# Constant_Register.net
KiCad netlist of a schematic drawn in EAGLE
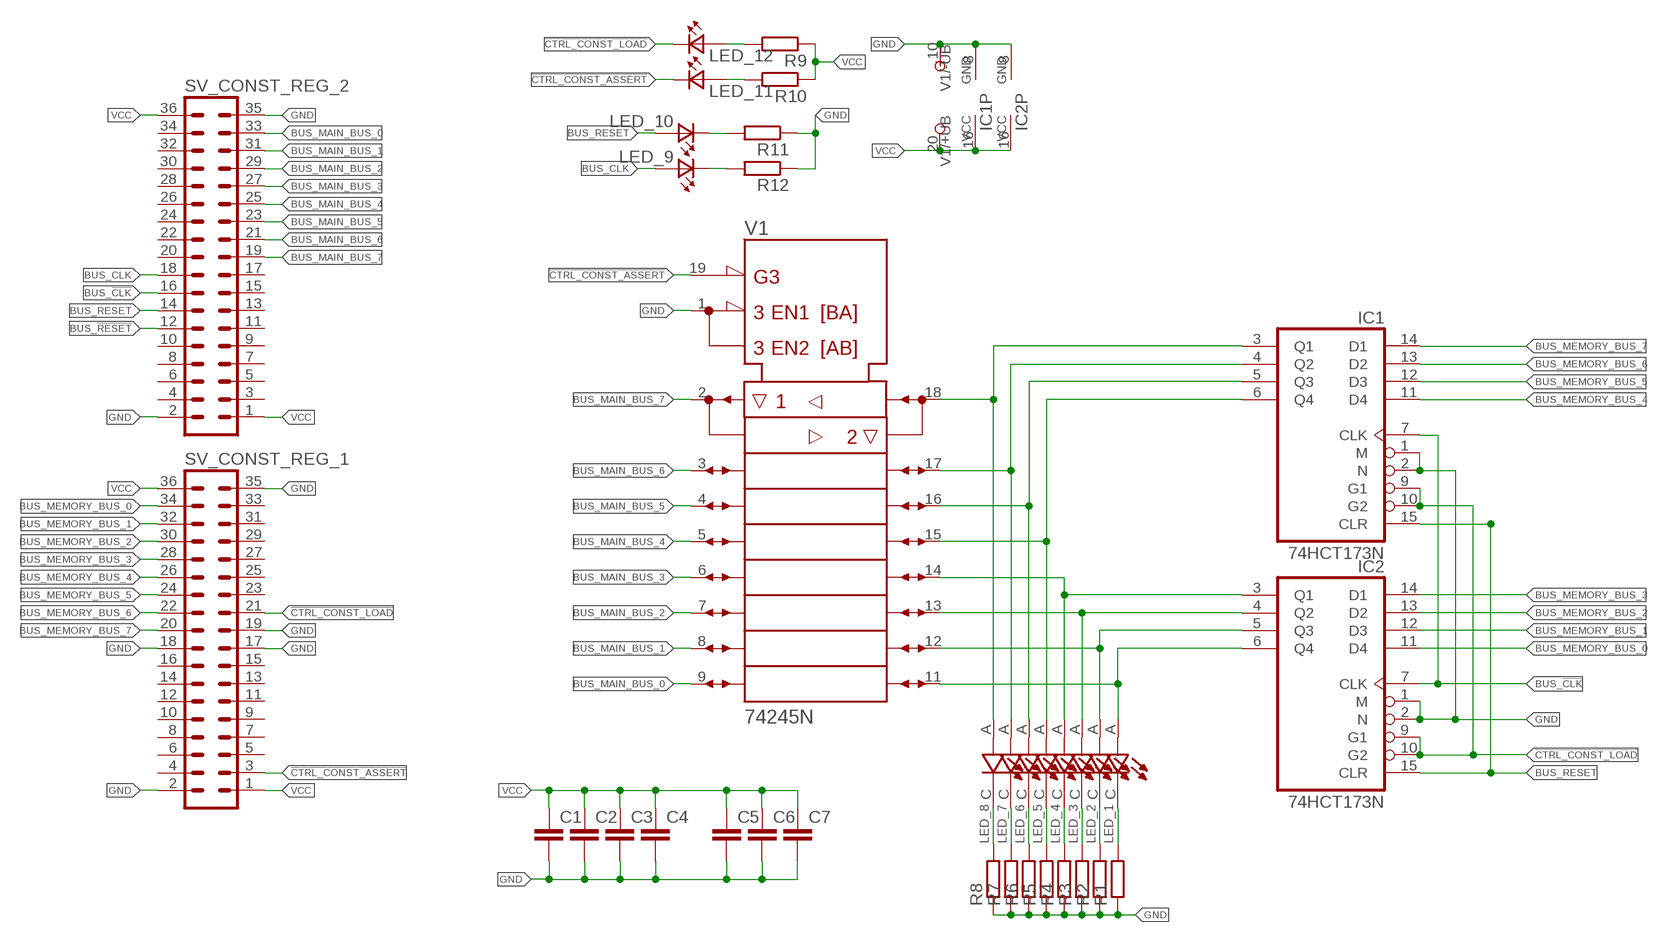
[diagram p0: schematic, sheet 1]

(export (version "E")
  (design (tool "Eeschema 10.0.6"))
  (components
    (comp (ref "C1")
      (value "C-EUC0805")
      (footprint "eagle-import:C0805")
      (libsource (lib "eagle-import") (part "C-EUC0805"))
    )
    (comp (ref "C2")
      (value "C-EUC0805")
      (footprint "eagle-import:C0805")
      (libsource (lib "eagle-import") (part "C-EUC0805"))
    )
    (comp (ref "C3")
      (value "C-EUC0805")
      (footprint "eagle-import:C0805")
      (libsource (lib "eagle-import") (part "C-EUC0805"))
    )
    (comp (ref "C4")
      (value "C-EUC0805")
      (footprint "eagle-import:C0805")
      (libsource (lib "eagle-import") (part "C-EUC0805"))
    )
    (comp (ref "C5")
      (value "C-EUC0805")
      (footprint "eagle-import:C0805")
      (libsource (lib "eagle-import") (part "C-EUC0805"))
    )
    (comp (ref "C6")
      (value "C-EUC0805")
      (footprint "eagle-import:C0805")
      (libsource (lib "eagle-import") (part "C-EUC0805"))
    )
    (comp (ref "C7")
      (value "C-EUC0805")
      (footprint "eagle-import:C0805")
      (libsource (lib "eagle-import") (part "C-EUC0805"))
    )
    (comp (ref "IC1")
      (value "74HCT173N")
      (footprint "eagle-import:DIL16")
      (libsource (lib "eagle-import") (part "74173NHCT"))
    )
    (comp (ref "IC2")
      (value "74HCT173N")
      (footprint "eagle-import:DIL16")
      (libsource (lib "eagle-import") (part "74173NHCT"))
    )
    (comp (ref "LED_1")
      (value "LTST-C193KRKT-5A")
      (footprint "eagle-import:LEDC1608X45N")
      (fields (field (name "MANUFACTURER") "Lite-On"))
      (libsource (lib "eagle-import") (part "LTST-C193KRKT-5A"))
    )
    (comp (ref "LED_2")
      (value "LTST-C193KRKT-5A")
      (footprint "eagle-import:LEDC1608X45N")
      (fields (field (name "MANUFACTURER") "Lite-On"))
      (libsource (lib "eagle-import") (part "LTST-C193KRKT-5A"))
    )
    (comp (ref "LED_3")
      (value "LTST-C193KRKT-5A")
      (footprint "eagle-import:LEDC1608X45N")
      (fields (field (name "MANUFACTURER") "Lite-On"))
      (libsource (lib "eagle-import") (part "LTST-C193KRKT-5A"))
    )
    (comp (ref "LED_4")
      (value "LTST-C193KRKT-5A")
      (footprint "eagle-import:LEDC1608X45N")
      (fields (field (name "MANUFACTURER") "Lite-On"))
      (libsource (lib "eagle-import") (part "LTST-C193KRKT-5A"))
    )
    (comp (ref "LED_5")
      (value "LTST-C193KRKT-5A")
      (footprint "eagle-import:LEDC1608X45N")
      (fields (field (name "MANUFACTURER") "Lite-On"))
      (libsource (lib "eagle-import") (part "LTST-C193KRKT-5A"))
    )
    (comp (ref "LED_6")
      (value "LTST-C193KRKT-5A")
      (footprint "eagle-import:LEDC1608X45N")
      (fields (field (name "MANUFACTURER") "Lite-On"))
      (libsource (lib "eagle-import") (part "LTST-C193KRKT-5A"))
    )
    (comp (ref "LED_7")
      (value "LTST-C193KRKT-5A")
      (footprint "eagle-import:LEDC1608X45N")
      (fields (field (name "MANUFACTURER") "Lite-On"))
      (libsource (lib "eagle-import") (part "LTST-C193KRKT-5A"))
    )
    (comp (ref "LED_8")
      (value "LTST-C193KRKT-5A")
      (footprint "eagle-import:LEDC1608X45N")
      (fields (field (name "MANUFACTURER") "Lite-On"))
      (libsource (lib "eagle-import") (part "LTST-C193KRKT-5A"))
    )
    (comp (ref "LED_9")
      (value "LTST-C193TBKT-5A")
      (footprint "eagle-import:0603")
      (libsource (lib "eagle-import") (part "LTST-C193TBKT-5A"))
    )
    (comp (ref "LED_10")
      (value "LTST-C193TBKT-5A")
      (footprint "eagle-import:0603")
      (libsource (lib "eagle-import") (part "LTST-C193TBKT-5A"))
    )
    (comp (ref "LED_11")
      (value "LTST-C193TBKT-5A")
      (footprint "eagle-import:0603")
      (libsource (lib "eagle-import") (part "LTST-C193TBKT-5A"))
    )
    (comp (ref "LED_12")
      (value "LTST-C193TBKT-5A")
      (footprint "eagle-import:0603")
      (libsource (lib "eagle-import") (part "LTST-C193TBKT-5A"))
    )
    (comp (ref "R1")
      (value "R-EU_R0805")
      (footprint "eagle-import:R0805")
      (libsource (lib "eagle-import") (part "R-EU_R0805"))
    )
    (comp (ref "R2")
      (value "R-EU_R0805")
      (footprint "eagle-import:R0805")
      (libsource (lib "eagle-import") (part "R-EU_R0805"))
    )
    (comp (ref "R3")
      (value "R-EU_R0805")
      (footprint "eagle-import:R0805")
      (libsource (lib "eagle-import") (part "R-EU_R0805"))
    )
    (comp (ref "R4")
      (value "R-EU_R0805")
      (footprint "eagle-import:R0805")
      (libsource (lib "eagle-import") (part "R-EU_R0805"))
    )
    (comp (ref "R5")
      (value "R-EU_R0805")
      (footprint "eagle-import:R0805")
      (libsource (lib "eagle-import") (part "R-EU_R0805"))
    )
    (comp (ref "R6")
      (value "R-EU_R0805")
      (footprint "eagle-import:R0805")
      (libsource (lib "eagle-import") (part "R-EU_R0805"))
    )
    (comp (ref "R7")
      (value "R-EU_R0805")
      (footprint "eagle-import:R0805")
      (libsource (lib "eagle-import") (part "R-EU_R0805"))
    )
    (comp (ref "R8")
      (value "R-EU_R0805")
      (footprint "eagle-import:R0805")
      (libsource (lib "eagle-import") (part "R-EU_R0805"))
    )
    (comp (ref "R9")
      (value "R-EU_R0805")
      (footprint "eagle-import:R0805")
      (libsource (lib "eagle-import") (part "R-EU_R0805"))
    )
    (comp (ref "R10")
      (value "R-EU_R0805")
      (footprint "eagle-import:R0805")
      (libsource (lib "eagle-import") (part "R-EU_R0805"))
    )
    (comp (ref "R11")
      (value "R-EU_R0805")
      (footprint "eagle-import:R0805")
      (libsource (lib "eagle-import") (part "R-EU_R0805"))
    )
    (comp (ref "R12")
      (value "R-EU_R0805")
      (footprint "eagle-import:R0805")
      (libsource (lib "eagle-import") (part "R-EU_R0805"))
    )
    (comp (ref "SV_CONST_REG_1")
      (value "MA18-2")
      (footprint "eagle-import:MA18-2")
      (libsource (lib "eagle-import") (part "MA18-2"))
    )
    (comp (ref "SV_CONST_REG_2")
      (value "MA18-2")
      (footprint "eagle-import:MA18-2")
      (libsource (lib "eagle-import") (part "MA18-2"))
    )
    (comp (ref "V1")
      (value "74245N")
      (footprint "eagle-import:DIL20")
      (libsource (lib "eagle-import") (part "74245N"))
    )
  )
  (nets
    (net (code "1") (name "/BUS_~{CLK}") (class "Default")
      (node (ref "IC1") (pin "7") (pinfunction "CLK_7") (pintype "input"))
      (node (ref "IC2") (pin "7") (pinfunction "CLK_7") (pintype "input"))
      (node (ref "SV_CONST_REG_2") (pin "16") (pinfunction "16_16") (pintype "passive"))
    )
    (net (code "2") (name "/BUS_~{RESET}") (class "Default")
      (node (ref "SV_CONST_REG_2") (pin "12") (pinfunction "12_12") (pintype "passive"))
    )
    (net (code "3") (name "/~{CTRL_CONST_ASSERT}") (class "Default")
      (node (ref "LED_11") (pin "1") (pinfunction "K2_1") (pintype "passive"))
      (node (ref "SV_CONST_REG_1") (pin "3") (pinfunction "3_3") (pintype "passive"))
      (node (ref "V1") (pin "19") (pinfunction "~{G}_19") (pintype "input"))
    )
    (net (code "4") (name "/~{CTRL_CONST_LOAD}") (class "Default")
      (node (ref "IC1") (pin "10") (pinfunction "G2_10") (pintype "input"))
      (node (ref "IC1") (pin "9") (pinfunction "G1_9") (pintype "input"))
      (node (ref "IC2") (pin "10") (pinfunction "G2_10") (pintype "input"))
      (node (ref "IC2") (pin "9") (pinfunction "G1_9") (pintype "input"))
      (node (ref "LED_12") (pin "1") (pinfunction "K2_1") (pintype "passive"))
      (node (ref "SV_CONST_REG_1") (pin "21") (pinfunction "21_21") (pintype "passive"))
    )
    (net (code "5") (name "BUS_CLK") (class "Default")
      (node (ref "LED_9") (pin "2") (pinfunction "A2_2") (pintype "passive"))
      (node (ref "SV_CONST_REG_2") (pin "18") (pinfunction "18_18") (pintype "passive"))
    )
    (net (code "6") (name "BUS_MAIN_BUS_0") (class "Default")
      (node (ref "SV_CONST_REG_2") (pin "33") (pinfunction "33_33") (pintype "passive"))
      (node (ref "V1") (pin "9") (pinfunction "A8_9") (pintype "bidirectional"))
    )
    (net (code "7") (name "BUS_MAIN_BUS_1") (class "Default")
      (node (ref "SV_CONST_REG_2") (pin "31") (pinfunction "31_31") (pintype "passive"))
      (node (ref "V1") (pin "8") (pinfunction "A7_8") (pintype "bidirectional"))
    )
    (net (code "8") (name "BUS_MAIN_BUS_2") (class "Default")
      (node (ref "SV_CONST_REG_2") (pin "29") (pinfunction "29_29") (pintype "passive"))
      (node (ref "V1") (pin "7") (pinfunction "A6_7") (pintype "bidirectional"))
    )
    (net (code "9") (name "BUS_MAIN_BUS_3") (class "Default")
      (node (ref "SV_CONST_REG_2") (pin "27") (pinfunction "27_27") (pintype "passive"))
      (node (ref "V1") (pin "6") (pinfunction "A5_6") (pintype "bidirectional"))
    )
    (net (code "10") (name "BUS_MAIN_BUS_4") (class "Default")
      (node (ref "SV_CONST_REG_2") (pin "25") (pinfunction "25_25") (pintype "passive"))
      (node (ref "V1") (pin "5") (pinfunction "A4_5") (pintype "bidirectional"))
    )
    (net (code "11") (name "BUS_MAIN_BUS_5") (class "Default")
      (node (ref "SV_CONST_REG_2") (pin "23") (pinfunction "23_23") (pintype "passive"))
      (node (ref "V1") (pin "4") (pinfunction "A3_4") (pintype "bidirectional"))
    )
    (net (code "12") (name "BUS_MAIN_BUS_6") (class "Default")
      (node (ref "SV_CONST_REG_2") (pin "21") (pinfunction "21_21") (pintype "passive"))
      (node (ref "V1") (pin "3") (pinfunction "A2_3") (pintype "bidirectional"))
    )
    (net (code "13") (name "BUS_MAIN_BUS_7") (class "Default")
      (node (ref "SV_CONST_REG_2") (pin "19") (pinfunction "19_19") (pintype "passive"))
      (node (ref "V1") (pin "2") (pinfunction "A1_2") (pintype "bidirectional"))
    )
    (net (code "14") (name "BUS_MEMORY_BUS_0") (class "Default")
      (node (ref "IC2") (pin "11") (pinfunction "D4_11") (pintype "input"))
      (node (ref "SV_CONST_REG_1") (pin "34") (pinfunction "34_34") (pintype "passive"))
    )
    (net (code "15") (name "BUS_MEMORY_BUS_1") (class "Default")
      (node (ref "IC2") (pin "12") (pinfunction "D3_12") (pintype "input"))
      (node (ref "SV_CONST_REG_1") (pin "32") (pinfunction "32_32") (pintype "passive"))
    )
    (net (code "16") (name "BUS_MEMORY_BUS_2") (class "Default")
      (node (ref "IC2") (pin "13") (pinfunction "D2_13") (pintype "input"))
      (node (ref "SV_CONST_REG_1") (pin "30") (pinfunction "30_30") (pintype "passive"))
    )
    (net (code "17") (name "BUS_MEMORY_BUS_3") (class "Default")
      (node (ref "IC2") (pin "14") (pinfunction "D1_14") (pintype "input"))
      (node (ref "SV_CONST_REG_1") (pin "28") (pinfunction "28_28") (pintype "passive"))
    )
    (net (code "18") (name "BUS_MEMORY_BUS_4") (class "Default")
      (node (ref "IC1") (pin "11") (pinfunction "D4_11") (pintype "input"))
      (node (ref "SV_CONST_REG_1") (pin "26") (pinfunction "26_26") (pintype "passive"))
    )
    (net (code "19") (name "BUS_MEMORY_BUS_5") (class "Default")
      (node (ref "IC1") (pin "12") (pinfunction "D3_12") (pintype "input"))
      (node (ref "SV_CONST_REG_1") (pin "24") (pinfunction "24_24") (pintype "passive"))
    )
    (net (code "20") (name "BUS_MEMORY_BUS_6") (class "Default")
      (node (ref "IC1") (pin "13") (pinfunction "D2_13") (pintype "input"))
      (node (ref "SV_CONST_REG_1") (pin "22") (pinfunction "22_22") (pintype "passive"))
    )
    (net (code "21") (name "BUS_MEMORY_BUS_7") (class "Default")
      (node (ref "IC1") (pin "14") (pinfunction "D1_14") (pintype "input"))
      (node (ref "SV_CONST_REG_1") (pin "20") (pinfunction "20_20") (pintype "passive"))
    )
    (net (code "22") (name "BUS_RESET") (class "Default")
      (node (ref "IC1") (pin "15") (pinfunction "CLR_15") (pintype "input"))
      (node (ref "IC2") (pin "15") (pinfunction "CLR_15") (pintype "input"))
      (node (ref "LED_10") (pin "2") (pinfunction "A2_2") (pintype "passive"))
      (node (ref "SV_CONST_REG_2") (pin "14") (pinfunction "14_14") (pintype "passive"))
    )
    (net (code "23") (name "GND") (class "Default")
      (node (ref "C1") (pin "2") (pinfunction "2_2") (pintype "passive"))
      (node (ref "C2") (pin "2") (pinfunction "2_2") (pintype "passive"))
      (node (ref "C3") (pin "2") (pinfunction "2_2") (pintype "passive"))
      (node (ref "C4") (pin "2") (pinfunction "2_2") (pintype "passive"))
      (node (ref "C5") (pin "2") (pinfunction "2_2") (pintype "passive"))
      (node (ref "C6") (pin "2") (pinfunction "2_2") (pintype "passive"))
      (node (ref "C7") (pin "2") (pinfunction "2_2") (pintype "passive"))
      (node (ref "IC1") (pin "1") (pinfunction "M_1") (pintype "input"))
      (node (ref "IC1") (pin "2") (pinfunction "N_2") (pintype "input"))
      (node (ref "IC1") (pin "8") (pinfunction "GND_8") (pintype "power_in"))
      (node (ref "IC2") (pin "1") (pinfunction "M_1") (pintype "input"))
      (node (ref "IC2") (pin "2") (pinfunction "N_2") (pintype "input"))
      (node (ref "IC2") (pin "8") (pinfunction "GND_8") (pintype "power_in"))
      (node (ref "R1") (pin "1") (pinfunction "1_1") (pintype "passive"))
      (node (ref "R11") (pin "1") (pinfunction "1_1") (pintype "passive"))
      (node (ref "R12") (pin "1") (pinfunction "1_1") (pintype "passive"))
      (node (ref "R2") (pin "1") (pinfunction "1_1") (pintype "passive"))
      (node (ref "R3") (pin "1") (pinfunction "1_1") (pintype "passive"))
      (node (ref "R4") (pin "1") (pinfunction "1_1") (pintype "passive"))
      (node (ref "R5") (pin "1") (pinfunction "1_1") (pintype "passive"))
      (node (ref "R6") (pin "1") (pinfunction "1_1") (pintype "passive"))
      (node (ref "R7") (pin "1") (pinfunction "1_1") (pintype "passive"))
      (node (ref "R8") (pin "1") (pinfunction "1_1") (pintype "passive"))
      (node (ref "SV_CONST_REG_1") (pin "17") (pinfunction "17_17") (pintype "passive"))
      (node (ref "SV_CONST_REG_1") (pin "18") (pinfunction "18_18") (pintype "passive"))
      (node (ref "SV_CONST_REG_1") (pin "19") (pinfunction "19_19") (pintype "passive"))
      (node (ref "SV_CONST_REG_1") (pin "2") (pinfunction "2_2") (pintype "passive"))
      (node (ref "SV_CONST_REG_1") (pin "35") (pinfunction "35_35") (pintype "passive"))
      (node (ref "SV_CONST_REG_2") (pin "2") (pinfunction "2_2") (pintype "passive"))
      (node (ref "SV_CONST_REG_2") (pin "35") (pinfunction "35_35") (pintype "passive"))
      (node (ref "V1") (pin "1") (pinfunction "DIR_1") (pintype "input"))
      (node (ref "V1") (pin "10") (pinfunction "-UB_10") (pintype "power_in"))
    )
    (net (code "24") (name "Net-(IC1A-Q1)") (class "Default")
      (node (ref "IC1") (pin "3") (pinfunction "Q1_3") (pintype "tri_state"))
      (node (ref "LED_8") (pin "A") (pinfunction "A_A") (pintype "passive"))
      (node (ref "V1") (pin "18") (pinfunction "B1_18") (pintype "bidirectional"))
    )
    (net (code "25") (name "Net-(IC1A-Q2)") (class "Default")
      (node (ref "IC1") (pin "4") (pinfunction "Q2_4") (pintype "tri_state"))
      (node (ref "LED_7") (pin "A") (pinfunction "A_A") (pintype "passive"))
      (node (ref "V1") (pin "17") (pinfunction "B2_17") (pintype "bidirectional"))
    )
    (net (code "26") (name "Net-(IC1A-Q3)") (class "Default")
      (node (ref "IC1") (pin "5") (pinfunction "Q3_5") (pintype "tri_state"))
      (node (ref "LED_6") (pin "A") (pinfunction "A_A") (pintype "passive"))
      (node (ref "V1") (pin "16") (pinfunction "B3_16") (pintype "bidirectional"))
    )
    (net (code "27") (name "Net-(IC1A-Q4)") (class "Default")
      (node (ref "IC1") (pin "6") (pinfunction "Q4_6") (pintype "tri_state"))
      (node (ref "LED_5") (pin "A") (pinfunction "A_A") (pintype "passive"))
      (node (ref "V1") (pin "15") (pinfunction "B4_15") (pintype "bidirectional"))
    )
    (net (code "28") (name "Net-(IC2A-Q1)") (class "Default")
      (node (ref "IC2") (pin "3") (pinfunction "Q1_3") (pintype "tri_state"))
      (node (ref "LED_4") (pin "A") (pinfunction "A_A") (pintype "passive"))
      (node (ref "V1") (pin "14") (pinfunction "B5_14") (pintype "bidirectional"))
    )
    (net (code "29") (name "Net-(IC2A-Q2)") (class "Default")
      (node (ref "IC2") (pin "4") (pinfunction "Q2_4") (pintype "tri_state"))
      (node (ref "LED_3") (pin "A") (pinfunction "A_A") (pintype "passive"))
      (node (ref "V1") (pin "13") (pinfunction "B6_13") (pintype "bidirectional"))
    )
    (net (code "30") (name "Net-(IC2A-Q3)") (class "Default")
      (node (ref "IC2") (pin "5") (pinfunction "Q3_5") (pintype "tri_state"))
      (node (ref "LED_2") (pin "A") (pinfunction "A_A") (pintype "passive"))
      (node (ref "V1") (pin "12") (pinfunction "B7_12") (pintype "bidirectional"))
    )
    (net (code "31") (name "Net-(IC2A-Q4)") (class "Default")
      (node (ref "IC2") (pin "6") (pinfunction "Q4_6") (pintype "tri_state"))
      (node (ref "LED_1") (pin "A") (pinfunction "A_A") (pintype "passive"))
      (node (ref "V1") (pin "11") (pinfunction "B8_11") (pintype "bidirectional"))
    )
    (net (code "32") (name "Net-(LED_1-PadC)") (class "Default")
      (node (ref "LED_1") (pin "C") (pinfunction "C_C") (pintype "passive"))
      (node (ref "R1") (pin "2") (pinfunction "2_2") (pintype "passive"))
    )
    (net (code "33") (name "Net-(LED_2-PadC)") (class "Default")
      (node (ref "LED_2") (pin "C") (pinfunction "C_C") (pintype "passive"))
      (node (ref "R2") (pin "2") (pinfunction "2_2") (pintype "passive"))
    )
    (net (code "34") (name "Net-(LED_3-PadC)") (class "Default")
      (node (ref "LED_3") (pin "C") (pinfunction "C_C") (pintype "passive"))
      (node (ref "R3") (pin "2") (pinfunction "2_2") (pintype "passive"))
    )
    (net (code "35") (name "Net-(LED_4-PadC)") (class "Default")
      (node (ref "LED_4") (pin "C") (pinfunction "C_C") (pintype "passive"))
      (node (ref "R4") (pin "2") (pinfunction "2_2") (pintype "passive"))
    )
    (net (code "36") (name "Net-(LED_5-PadC)") (class "Default")
      (node (ref "LED_5") (pin "C") (pinfunction "C_C") (pintype "passive"))
      (node (ref "R5") (pin "2") (pinfunction "2_2") (pintype "passive"))
    )
    (net (code "37") (name "Net-(LED_6-PadC)") (class "Default")
      (node (ref "LED_6") (pin "C") (pinfunction "C_C") (pintype "passive"))
      (node (ref "R6") (pin "2") (pinfunction "2_2") (pintype "passive"))
    )
    (net (code "38") (name "Net-(LED_7-PadC)") (class "Default")
      (node (ref "LED_7") (pin "C") (pinfunction "C_C") (pintype "passive"))
      (node (ref "R7") (pin "2") (pinfunction "2_2") (pintype "passive"))
    )
    (net (code "39") (name "Net-(LED_8-PadC)") (class "Default")
      (node (ref "LED_8") (pin "C") (pinfunction "C_C") (pintype "passive"))
      (node (ref "R8") (pin "2") (pinfunction "2_2") (pintype "passive"))
    )
    (net (code "40") (name "Net-(LED_9-K2)") (class "Default")
      (node (ref "LED_9") (pin "1") (pinfunction "K2_1") (pintype "passive"))
      (node (ref "R12") (pin "2") (pinfunction "2_2") (pintype "passive"))
    )
    (net (code "41") (name "Net-(LED_10-K2)") (class "Default")
      (node (ref "LED_10") (pin "1") (pinfunction "K2_1") (pintype "passive"))
      (node (ref "R11") (pin "2") (pinfunction "2_2") (pintype "passive"))
    )
    (net (code "42") (name "Net-(LED_11-A2)") (class "Default")
      (node (ref "LED_11") (pin "2") (pinfunction "A2_2") (pintype "passive"))
      (node (ref "R10") (pin "2") (pinfunction "2_2") (pintype "passive"))
    )
    (net (code "43") (name "Net-(LED_12-A2)") (class "Default")
      (node (ref "LED_12") (pin "2") (pinfunction "A2_2") (pintype "passive"))
      (node (ref "R9") (pin "2") (pinfunction "2_2") (pintype "passive"))
    )
    (net (code "44") (name "VCC") (class "Default")
      (node (ref "C1") (pin "1") (pinfunction "1_1") (pintype "passive"))
      (node (ref "C2") (pin "1") (pinfunction "1_1") (pintype "passive"))
      (node (ref "C3") (pin "1") (pinfunction "1_1") (pintype "passive"))
      (node (ref "C4") (pin "1") (pinfunction "1_1") (pintype "passive"))
      (node (ref "C5") (pin "1") (pinfunction "1_1") (pintype "passive"))
      (node (ref "C6") (pin "1") (pinfunction "1_1") (pintype "passive"))
      (node (ref "C7") (pin "1") (pinfunction "1_1") (pintype "passive"))
      (node (ref "IC1") (pin "16") (pinfunction "VCC_16") (pintype "power_in"))
      (node (ref "IC2") (pin "16") (pinfunction "VCC_16") (pintype "power_in"))
      (node (ref "R10") (pin "1") (pinfunction "1_1") (pintype "passive"))
      (node (ref "R9") (pin "1") (pinfunction "1_1") (pintype "passive"))
      (node (ref "SV_CONST_REG_1") (pin "1") (pinfunction "1_1") (pintype "passive"))
      (node (ref "SV_CONST_REG_1") (pin "36") (pinfunction "36_36") (pintype "passive"))
      (node (ref "SV_CONST_REG_2") (pin "1") (pinfunction "1_1") (pintype "passive"))
      (node (ref "SV_CONST_REG_2") (pin "36") (pinfunction "36_36") (pintype "passive"))
      (node (ref "V1") (pin "20") (pinfunction "+UB_20") (pintype "power_in"))
    )
    (net (code "45") (name "unconnected-(SV_CONST_REG_1-Pad4)") (class "Default")
      (node (ref "SV_CONST_REG_1") (pin "4") (pinfunction "4_4") (pintype "passive"))
    )
    (net (code "46") (name "unconnected-(SV_CONST_REG_1-Pad5)") (class "Default")
      (node (ref "SV_CONST_REG_1") (pin "5") (pinfunction "5_5") (pintype "passive"))
    )
    (net (code "47") (name "unconnected-(SV_CONST_REG_1-Pad6)") (class "Default")
      (node (ref "SV_CONST_REG_1") (pin "6") (pinfunction "6_6") (pintype "passive"))
    )
    (net (code "48") (name "unconnected-(SV_CONST_REG_1-Pad7)") (class "Default")
      (node (ref "SV_CONST_REG_1") (pin "7") (pinfunction "7_7") (pintype "passive"))
    )
    (net (code "49") (name "unconnected-(SV_CONST_REG_1-Pad8)") (class "Default")
      (node (ref "SV_CONST_REG_1") (pin "8") (pinfunction "8_8") (pintype "passive"))
    )
    (net (code "50") (name "unconnected-(SV_CONST_REG_1-Pad9)") (class "Default")
      (node (ref "SV_CONST_REG_1") (pin "9") (pinfunction "9_9") (pintype "passive"))
    )
    (net (code "51") (name "unconnected-(SV_CONST_REG_1-Pad10)") (class "Default")
      (node (ref "SV_CONST_REG_1") (pin "10") (pinfunction "10_10") (pintype "passive"))
    )
    (net (code "52") (name "unconnected-(SV_CONST_REG_1-Pad11)") (class "Default")
      (node (ref "SV_CONST_REG_1") (pin "11") (pinfunction "11_11") (pintype "passive"))
    )
    (net (code "53") (name "unconnected-(SV_CONST_REG_1-Pad12)") (class "Default")
      (node (ref "SV_CONST_REG_1") (pin "12") (pinfunction "12_12") (pintype "passive"))
    )
    (net (code "54") (name "unconnected-(SV_CONST_REG_1-Pad13)") (class "Default")
      (node (ref "SV_CONST_REG_1") (pin "13") (pinfunction "13_13") (pintype "passive"))
    )
    (net (code "55") (name "unconnected-(SV_CONST_REG_1-Pad14)") (class "Default")
      (node (ref "SV_CONST_REG_1") (pin "14") (pinfunction "14_14") (pintype "passive"))
    )
    (net (code "56") (name "unconnected-(SV_CONST_REG_1-Pad15)") (class "Default")
      (node (ref "SV_CONST_REG_1") (pin "15") (pinfunction "15_15") (pintype "passive"))
    )
    (net (code "57") (name "unconnected-(SV_CONST_REG_1-Pad16)") (class "Default")
      (node (ref "SV_CONST_REG_1") (pin "16") (pinfunction "16_16") (pintype "passive"))
    )
    (net (code "58") (name "unconnected-(SV_CONST_REG_1-Pad23)") (class "Default")
      (node (ref "SV_CONST_REG_1") (pin "23") (pinfunction "23_23") (pintype "passive"))
    )
    (net (code "59") (name "unconnected-(SV_CONST_REG_1-Pad25)") (class "Default")
      (node (ref "SV_CONST_REG_1") (pin "25") (pinfunction "25_25") (pintype "passive"))
    )
    (net (code "60") (name "unconnected-(SV_CONST_REG_1-Pad27)") (class "Default")
      (node (ref "SV_CONST_REG_1") (pin "27") (pinfunction "27_27") (pintype "passive"))
    )
    (net (code "61") (name "unconnected-(SV_CONST_REG_1-Pad29)") (class "Default")
      (node (ref "SV_CONST_REG_1") (pin "29") (pinfunction "29_29") (pintype "passive"))
    )
    (net (code "62") (name "unconnected-(SV_CONST_REG_1-Pad31)") (class "Default")
      (node (ref "SV_CONST_REG_1") (pin "31") (pinfunction "31_31") (pintype "passive"))
    )
    (net (code "63") (name "unconnected-(SV_CONST_REG_1-Pad33)") (class "Default")
      (node (ref "SV_CONST_REG_1") (pin "33") (pinfunction "33_33") (pintype "passive"))
    )
    (net (code "64") (name "unconnected-(SV_CONST_REG_2-Pad3)") (class "Default")
      (node (ref "SV_CONST_REG_2") (pin "3") (pinfunction "3_3") (pintype "passive"))
    )
    (net (code "65") (name "unconnected-(SV_CONST_REG_2-Pad4)") (class "Default")
      (node (ref "SV_CONST_REG_2") (pin "4") (pinfunction "4_4") (pintype "passive"))
    )
    (net (code "66") (name "unconnected-(SV_CONST_REG_2-Pad5)") (class "Default")
      (node (ref "SV_CONST_REG_2") (pin "5") (pinfunction "5_5") (pintype "passive"))
    )
    (net (code "67") (name "unconnected-(SV_CONST_REG_2-Pad6)") (class "Default")
      (node (ref "SV_CONST_REG_2") (pin "6") (pinfunction "6_6") (pintype "passive"))
    )
    (net (code "68") (name "unconnected-(SV_CONST_REG_2-Pad7)") (class "Default")
      (node (ref "SV_CONST_REG_2") (pin "7") (pinfunction "7_7") (pintype "passive"))
    )
    (net (code "69") (name "unconnected-(SV_CONST_REG_2-Pad8)") (class "Default")
      (node (ref "SV_CONST_REG_2") (pin "8") (pinfunction "8_8") (pintype "passive"))
    )
    (net (code "70") (name "unconnected-(SV_CONST_REG_2-Pad9)") (class "Default")
      (node (ref "SV_CONST_REG_2") (pin "9") (pinfunction "9_9") (pintype "passive"))
    )
    (net (code "71") (name "unconnected-(SV_CONST_REG_2-Pad10)") (class "Default")
      (node (ref "SV_CONST_REG_2") (pin "10") (pinfunction "10_10") (pintype "passive"))
    )
    (net (code "72") (name "unconnected-(SV_CONST_REG_2-Pad11)") (class "Default")
      (node (ref "SV_CONST_REG_2") (pin "11") (pinfunction "11_11") (pintype "passive"))
    )
    (net (code "73") (name "unconnected-(SV_CONST_REG_2-Pad13)") (class "Default")
      (node (ref "SV_CONST_REG_2") (pin "13") (pinfunction "13_13") (pintype "passive"))
    )
    (net (code "74") (name "unconnected-(SV_CONST_REG_2-Pad15)") (class "Default")
      (node (ref "SV_CONST_REG_2") (pin "15") (pinfunction "15_15") (pintype "passive"))
    )
    (net (code "75") (name "unconnected-(SV_CONST_REG_2-Pad17)") (class "Default")
      (node (ref "SV_CONST_REG_2") (pin "17") (pinfunction "17_17") (pintype "passive"))
    )
    (net (code "76") (name "unconnected-(SV_CONST_REG_2-Pad20)") (class "Default")
      (node (ref "SV_CONST_REG_2") (pin "20") (pinfunction "20_20") (pintype "passive"))
    )
    (net (code "77") (name "unconnected-(SV_CONST_REG_2-Pad22)") (class "Default")
      (node (ref "SV_CONST_REG_2") (pin "22") (pinfunction "22_22") (pintype "passive"))
    )
    (net (code "78") (name "unconnected-(SV_CONST_REG_2-Pad24)") (class "Default")
      (node (ref "SV_CONST_REG_2") (pin "24") (pinfunction "24_24") (pintype "passive"))
    )
    (net (code "79") (name "unconnected-(SV_CONST_REG_2-Pad26)") (class "Default")
      (node (ref "SV_CONST_REG_2") (pin "26") (pinfunction "26_26") (pintype "passive"))
    )
    (net (code "80") (name "unconnected-(SV_CONST_REG_2-Pad28)") (class "Default")
      (node (ref "SV_CONST_REG_2") (pin "28") (pinfunction "28_28") (pintype "passive"))
    )
    (net (code "81") (name "unconnected-(SV_CONST_REG_2-Pad30)") (class "Default")
      (node (ref "SV_CONST_REG_2") (pin "30") (pinfunction "30_30") (pintype "passive"))
    )
    (net (code "82") (name "unconnected-(SV_CONST_REG_2-Pad32)") (class "Default")
      (node (ref "SV_CONST_REG_2") (pin "32") (pinfunction "32_32") (pintype "passive"))
    )
    (net (code "83") (name "unconnected-(SV_CONST_REG_2-Pad34)") (class "Default")
      (node (ref "SV_CONST_REG_2") (pin "34") (pinfunction "34_34") (pintype "passive"))
    )
  )
)
